# Sheet1.net
KiCad netlist of a schematic drawn in Altium Designer
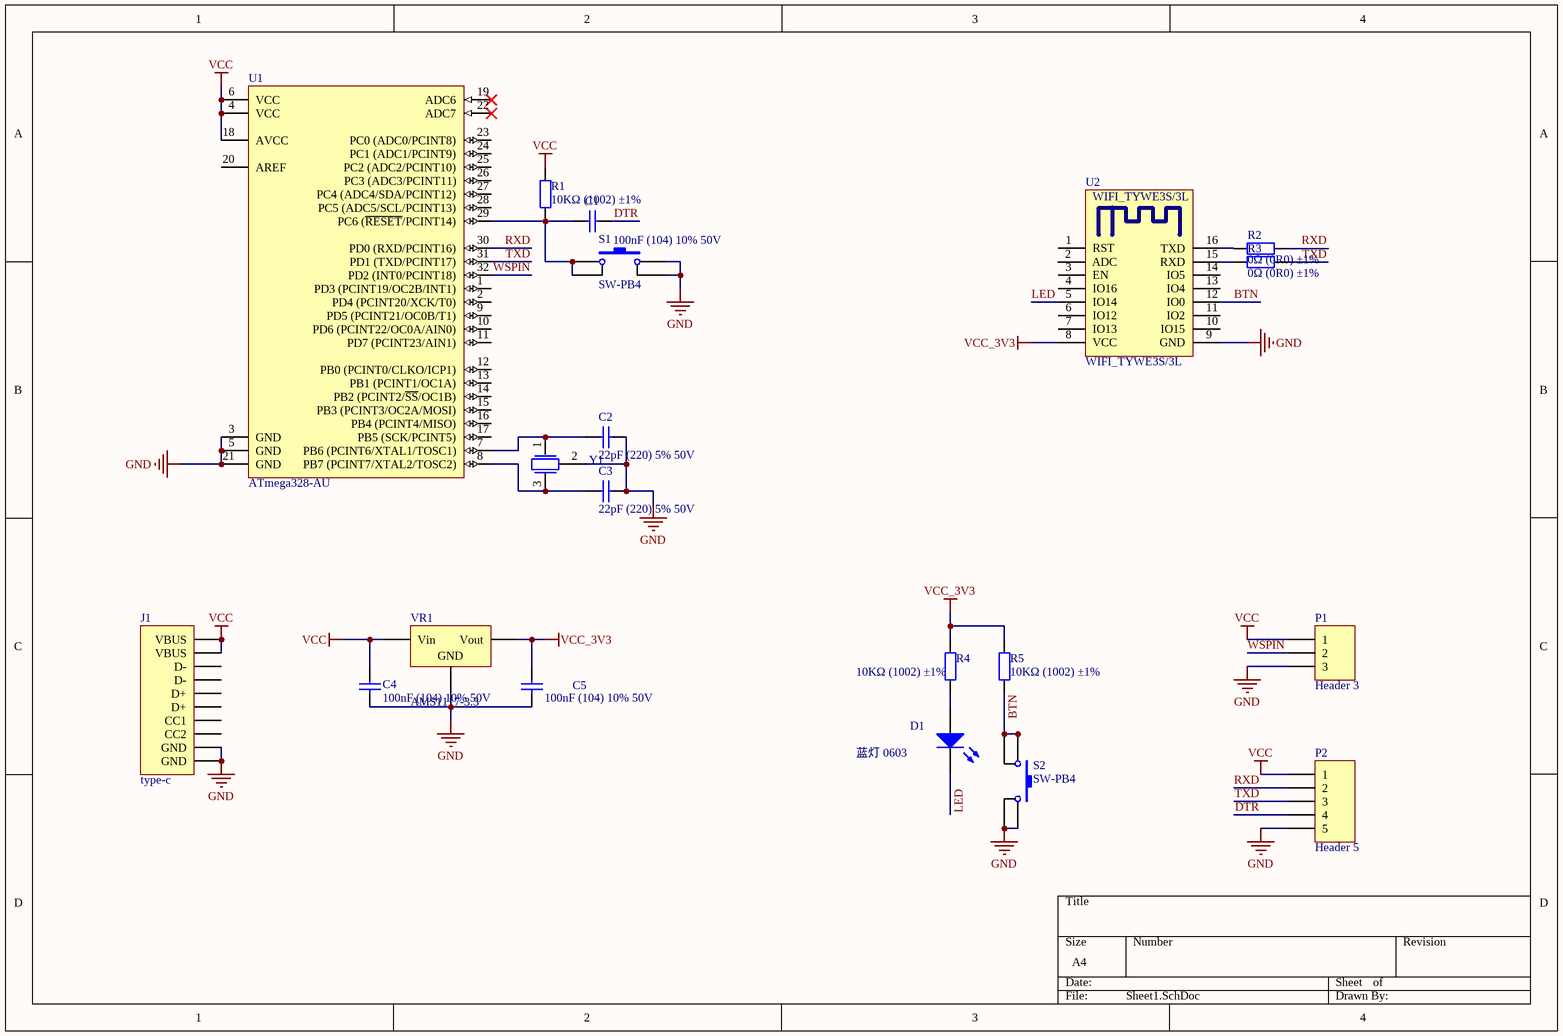
[diagram p0: Sheet1.SchDoc]

(export (version "E")
  (design (tool "Eeschema 10.0.6"))
  (components
    (comp (ref "C1")
      (value "100nF (104) 10% 50V")
      (footprint "LC-0603_C")
      (description "贴片电容")
      (libsource (lib "嘉立创库") (part "0603 100nF (104) 10% 50V"))
    )
    (comp (ref "C2")
      (value "22pF (220) 5% 50V")
      (footprint "LC-0603_C")
      (description "贴片电容")
      (libsource (lib "嘉立创库") (part "0603 22pF (220) 5% 50V"))
    )
    (comp (ref "C3")
      (value "22pF (220) 5% 50V")
      (footprint "LC-0603_C")
      (description "贴片电容")
      (libsource (lib "嘉立创库") (part "0603 22pF (220) 5% 50V"))
    )
    (comp (ref "C4")
      (value "100nF (104) 10% 50V")
      (footprint "LC-0603_C")
      (description "贴片电容")
      (libsource (lib "嘉立创库") (part "0603 100nF (104) 10% 50V"))
    )
    (comp (ref "C5")
      (value "100nF (104) 10% 50V")
      (footprint "LC-0603_C")
      (description "贴片电容")
      (libsource (lib "嘉立创库") (part "0603 100nF (104) 10% 50V"))
    )
    (comp (ref "D1")
      (value "蓝灯 0603")
      (footprint "LC-0603_LED_S1")
      (description "发光二极管")
      (libsource (lib "嘉立创库") (part "0603 蓝灯"))
    )
    (comp (ref "J1") (value "type-c") (footprint "type") (libsource (lib "Schlib_hqs") (part "type-c")))
    (comp (ref "P1")
      (value "Header 3")
      (footprint "XH2.54 3P")
      (description "Header, 3-Pin")
      (fields (field (name "PUBLISHER") "Altium Limited"))
      (libsource (lib "Miscellaneous Connectors") (part "Header 3"))
    )
    (comp (ref "P2")
      (value "Header 5")
      (footprint "HDR1X5")
      (description "Header, 5-Pin")
      (fields (field (name "PUBLISHER") "Altium Limited"))
      (libsource (lib "Miscellaneous Connectors") (part "Header 5"))
    )
    (comp (ref "R1")
      (value "10KΩ (1002) ±1%")
      (footprint "LC-0603_R")
      (description "贴片电阻")
      (libsource (lib "") (part "0603 10KΩ (1002) 1%_1"))
    )
    (comp (ref "R2")
      (value "0Ω (0R0) ±1%")
      (footprint "LC-0603_R")
      (description "贴片电阻")
      (libsource (lib "嘉立创库") (part "0603 0Ω (0R0) 1%"))
    )
    (comp (ref "R3")
      (value "0Ω (0R0) ±1%")
      (footprint "LC-0603_R")
      (description "贴片电阻")
      (libsource (lib "嘉立创库") (part "0603 0Ω (0R0) 1%"))
    )
    (comp (ref "R4")
      (value "10KΩ (1002) ±1%")
      (footprint "LC-0603_R")
      (description "贴片电阻")
      (libsource (lib "嘉立创库") (part "0603 10KΩ (1002) 1%"))
    )
    (comp (ref "R5")
      (value "10KΩ (1002) ±1%")
      (footprint "LC-0603_R")
      (description "贴片电阻")
      (libsource (lib "") (part "0603 10KΩ (1002) 1%_1"))
    )
    (comp (ref "S1")
      (value "SW-PB4")
      (footprint "SW_PB4_A1")
      (description "微动开关")
      (fields (field (name "PUBLISHER") "Altium Limited"))
      (libsource (lib "Fszhang") (part "SW-PB4"))
    )
    (comp (ref "S2")
      (value "SW-PB4")
      (footprint "SW_PB4_A1")
      (description "微动开关")
      (fields (field (name "PUBLISHER") "Altium Limited"))
      (libsource (lib "Fszhang") (part "SW-PB4"))
    )
    (comp (ref "U1")
      (value "ATmega328-AU")
      (footprint "32A_N")
      (fields (field (name "PUBLISHER") "Altium Limited"))
      (libsource (lib "Atmel Microcontroller 8-Bit megaAVR") (part "ATmega328-AU"))
    )
    (comp (ref "U2")
      (value "WIFI_TYWE3S/3L")
      (footprint "WIFI_TYWE3S/3L")
      (description "Module")
      (libsource (lib "TYModeSchlib") (part "WIFI_TYWE3S/3L"))
    )
    (comp (ref "VR1")
      (value "AMS1117-3.3")
      (footprint "LC-SOT-223")
      (description "低压差线性稳压(LDO)")
      (libsource (lib "嘉立创库") (part "SOT-223 AMS1117-3.3"))
    )
    (comp (ref "Y1")
      (value "XTAL-3PIN")
      (footprint "X-CPX20")
      (description "贴片晶振")
      (libsource (lib "Fszhang") (part "XTAL-3PIN"))
    )
  )
  (nets
    (net (code "1") (name "/BTN") (class "Default")
      (node (ref "R5") (pin "1") (pinfunction "1_1") (pintype "passive"))
      (node (ref "S2") (pin "1") (pinfunction "1_1") (pintype "passive"))
      (node (ref "S2") (pin "4") (pinfunction "4_4") (pintype "passive"))
      (node (ref "U2") (pin "12") (pinfunction "IO0_12") (pintype "passive"))
    )
    (net (code "2") (name "/DTR") (class "Default")
      (node (ref "C1") (pin "1") (pinfunction "1_1") (pintype "passive"))
      (node (ref "P2") (pin "4") (pinfunction "4_4") (pintype "passive"))
    )
    (net (code "3") (name "/LED") (class "Default")
      (node (ref "D1") (pin "K") (pinfunction "K_K") (pintype "passive"))
      (node (ref "U2") (pin "5") (pinfunction "IO14_5") (pintype "passive"))
    )
    (net (code "4") (name "/RXD") (class "Default")
      (node (ref "P2") (pin "2") (pinfunction "2_2") (pintype "passive"))
      (node (ref "R2") (pin "2") (pinfunction "2_2") (pintype "passive"))
      (node (ref "U1") (pin "30") (pinfunction "PD0_(RXD/PCINT16)_30") (pintype "bidirectional"))
    )
    (net (code "5") (name "/TXD") (class "Default")
      (node (ref "P2") (pin "3") (pinfunction "3_3") (pintype "passive"))
      (node (ref "R3") (pin "2") (pinfunction "2_2") (pintype "passive"))
      (node (ref "U1") (pin "31") (pinfunction "PD1_(TXD/PCINT17)_31") (pintype "bidirectional"))
    )
    (net (code "6") (name "/WSPIN") (class "Default")
      (node (ref "P1") (pin "2") (pinfunction "2_2") (pintype "passive"))
      (node (ref "U1") (pin "32") (pinfunction "PD2_(INT0/PCINT18)_32") (pintype "bidirectional"))
    )
    (net (code "7") (name "GND") (class "Default")
      (node (ref "C2") (pin "2") (pinfunction "2_2") (pintype "passive"))
      (node (ref "C3") (pin "2") (pinfunction "2_2") (pintype "passive"))
      (node (ref "C4") (pin "1") (pinfunction "1_1") (pintype "passive"))
      (node (ref "C5") (pin "1") (pinfunction "1_1") (pintype "passive"))
      (node (ref "J1") (pin "A12B1") (pinfunction "GND_A12B1") (pintype "passive"))
      (node (ref "J1") (pin "A1B12") (pinfunction "GND_A1B12") (pintype "passive"))
      (node (ref "P1") (pin "3") (pinfunction "3_3") (pintype "passive"))
      (node (ref "P2") (pin "5") (pinfunction "5_5") (pintype "passive"))
      (node (ref "S1") (pin "2") (pinfunction "2_2") (pintype "passive"))
      (node (ref "S1") (pin "3") (pinfunction "3_3") (pintype "passive"))
      (node (ref "S2") (pin "2") (pinfunction "2_2") (pintype "passive"))
      (node (ref "S2") (pin "3") (pinfunction "3_3") (pintype "passive"))
      (node (ref "U1") (pin "21") (pinfunction "GND_21") (pintype "power_in"))
      (node (ref "U1") (pin "3") (pinfunction "GND_3") (pintype "power_in"))
      (node (ref "U1") (pin "5") (pinfunction "GND_5") (pintype "power_in"))
      (node (ref "U2") (pin "9") (pinfunction "GND_9") (pintype "passive"))
      (node (ref "VR1") (pin "1") (pinfunction "GND_1") (pintype "passive"))
      (node (ref "Y1") (pin "2") (pinfunction "2_2") (pintype "passive"))
    )
    (net (code "8") (name "Net-(D1-PadA)") (class "Default")
      (node (ref "D1") (pin "A") (pinfunction "A_A") (pintype "passive"))
      (node (ref "R4") (pin "2") (pinfunction "2_2") (pintype "passive"))
    )
    (net (code "9") (name "Net-(U1-PB6_(PCINT6{slash}XTAL1{slash}TOSC1))") (class "Default")
      (node (ref "C2") (pin "1") (pinfunction "1_1") (pintype "passive"))
      (node (ref "U1") (pin "7") (pinfunction "PB6_(PCINT6/XTAL1/TOSC1)_7") (pintype "bidirectional"))
      (node (ref "Y1") (pin "1") (pinfunction "1_1") (pintype "passive"))
    )
    (net (code "10") (name "Net-(U1-PB7_(PCINT7{slash}XTAL2{slash}TOSC2))") (class "Default")
      (node (ref "C3") (pin "1") (pinfunction "1_1") (pintype "passive"))
      (node (ref "U1") (pin "8") (pinfunction "PB7_(PCINT7/XTAL2/TOSC2)_8") (pintype "bidirectional"))
      (node (ref "Y1") (pin "3") (pinfunction "3_3") (pintype "passive"))
    )
    (net (code "11") (name "Net-(U1-PC6_(~{RESET}{slash}PCINT14))") (class "Default")
      (node (ref "C1") (pin "2") (pinfunction "2_2") (pintype "passive"))
      (node (ref "R1") (pin "1") (pinfunction "1_1") (pintype "passive"))
      (node (ref "S1") (pin "1") (pinfunction "1_1") (pintype "passive"))
      (node (ref "S1") (pin "4") (pinfunction "4_4") (pintype "passive"))
      (node (ref "U1") (pin "29") (pinfunction "PC6_(~{RESET}/PCINT14)_29") (pintype "bidirectional"))
    )
    (net (code "12") (name "Net-(U2-RXD)") (class "Default")
      (node (ref "R3") (pin "1") (pinfunction "1_1") (pintype "passive"))
      (node (ref "U2") (pin "15") (pinfunction "RXD_15") (pintype "passive"))
    )
    (net (code "13") (name "Net-(U2-TXD)") (class "Default")
      (node (ref "R2") (pin "1") (pinfunction "1_1") (pintype "passive"))
      (node (ref "U2") (pin "16") (pinfunction "TXD_16") (pintype "passive"))
    )
    (net (code "14") (name "VCC") (class "Default")
      (node (ref "C4") (pin "2") (pinfunction "2_2") (pintype "passive"))
      (node (ref "J1") (pin "A4B9") (pinfunction "VBUS_A4B9") (pintype "passive"))
      (node (ref "J1") (pin "A9B4") (pinfunction "VBUS_A9B4") (pintype "passive"))
      (node (ref "P1") (pin "1") (pinfunction "1_1") (pintype "passive"))
      (node (ref "P2") (pin "1") (pinfunction "1_1") (pintype "passive"))
      (node (ref "R1") (pin "2") (pinfunction "2_2") (pintype "passive"))
      (node (ref "U1") (pin "18") (pinfunction "AVCC_18") (pintype "power_in"))
      (node (ref "U1") (pin "4") (pinfunction "VCC_4") (pintype "power_in"))
      (node (ref "U1") (pin "6") (pinfunction "VCC_6") (pintype "power_in"))
      (node (ref "VR1") (pin "3") (pinfunction "Vin_3") (pintype "passive"))
    )
    (net (code "15") (name "VCC_3V3") (class "Default")
      (node (ref "C5") (pin "2") (pinfunction "2_2") (pintype "passive"))
      (node (ref "R4") (pin "1") (pinfunction "1_1") (pintype "passive"))
      (node (ref "R5") (pin "2") (pinfunction "2_2") (pintype "passive"))
      (node (ref "U2") (pin "8") (pinfunction "VCC_8") (pintype "passive"))
      (node (ref "VR1") (pin "2") (pinfunction "Vout_2") (pintype "passive"))
    )
    (net (code "16") (name "unconnected-(J1-CC1-PadA5)") (class "Default")
      (node (ref "J1") (pin "A5") (pinfunction "CC1_A5") (pintype "passive"))
    )
    (net (code "17") (name "unconnected-(J1-CC2-PadB5)") (class "Default")
      (node (ref "J1") (pin "B5") (pinfunction "CC2_B5") (pintype "passive"))
    )
    (net (code "18") (name "unconnected-(J1-D+-PadA6)") (class "Default")
      (node (ref "J1") (pin "A6") (pinfunction "D+_A6") (pintype "passive"))
    )
    (net (code "19") (name "unconnected-(J1-D+-PadB6)") (class "Default")
      (node (ref "J1") (pin "B6") (pinfunction "D+_B6") (pintype "passive"))
    )
    (net (code "20") (name "unconnected-(J1-D--PadA7)") (class "Default")
      (node (ref "J1") (pin "A7") (pinfunction "D-_A7") (pintype "passive"))
    )
    (net (code "21") (name "unconnected-(J1-D--PadB7)") (class "Default")
      (node (ref "J1") (pin "B7") (pinfunction "D-_B7") (pintype "passive"))
    )
    (net (code "22") (name "unconnected-(U1-ADC6-Pad19)") (class "Default")
      (node (ref "U1") (pin "19") (pinfunction "ADC6_19") (pintype "input+no_connect"))
    )
    (net (code "23") (name "unconnected-(U1-ADC7-Pad22)") (class "Default")
      (node (ref "U1") (pin "22") (pinfunction "ADC7_22") (pintype "input+no_connect"))
    )
    (net (code "24") (name "unconnected-(U1-AREF-Pad20)") (class "Default")
      (node (ref "U1") (pin "20") (pinfunction "AREF_20") (pintype "passive"))
    )
    (net (code "25") (name "unconnected-(U1-PB0_(PCINT0{slash}CLKO{slash}ICP1)-Pad12)") (class "Default")
      (node (ref "U1") (pin "12") (pinfunction "PB0_(PCINT0/CLKO/ICP1)_12") (pintype "bidirectional"))
    )
    (net (code "26") (name "unconnected-(U1-PB1_(PCINT1{slash}OC1A)-Pad13)") (class "Default")
      (node (ref "U1") (pin "13") (pinfunction "PB1_(PCINT1/OC1A)_13") (pintype "bidirectional"))
    )
    (net (code "27") (name "unconnected-(U1-PB2_(PCINT2{slash}~{SS}{slash}OC1B)-Pad14)") (class "Default")
      (node (ref "U1") (pin "14") (pinfunction "PB2_(PCINT2/~{SS}/OC1B)_14") (pintype "bidirectional"))
    )
    (net (code "28") (name "unconnected-(U1-PB3_(PCINT3{slash}OC2A{slash}MOSI)-Pad15)") (class "Default")
      (node (ref "U1") (pin "15") (pinfunction "PB3_(PCINT3/OC2A/MOSI)_15") (pintype "bidirectional"))
    )
    (net (code "29") (name "unconnected-(U1-PB4_(PCINT4{slash}MISO)-Pad16)") (class "Default")
      (node (ref "U1") (pin "16") (pinfunction "PB4_(PCINT4/MISO)_16") (pintype "bidirectional"))
    )
    (net (code "30") (name "unconnected-(U1-PB5_(SCK{slash}PCINT5)-Pad17)") (class "Default")
      (node (ref "U1") (pin "17") (pinfunction "PB5_(SCK/PCINT5)_17") (pintype "bidirectional"))
    )
    (net (code "31") (name "unconnected-(U1-PC0_(ADC0{slash}PCINT8)-Pad23)") (class "Default")
      (node (ref "U1") (pin "23") (pinfunction "PC0_(ADC0/PCINT8)_23") (pintype "bidirectional"))
    )
    (net (code "32") (name "unconnected-(U1-PC1_(ADC1{slash}PCINT9)-Pad24)") (class "Default")
      (node (ref "U1") (pin "24") (pinfunction "PC1_(ADC1/PCINT9)_24") (pintype "bidirectional"))
    )
    (net (code "33") (name "unconnected-(U1-PC2_(ADC2{slash}PCINT10)-Pad25)") (class "Default")
      (node (ref "U1") (pin "25") (pinfunction "PC2_(ADC2/PCINT10)_25") (pintype "bidirectional"))
    )
    (net (code "34") (name "unconnected-(U1-PC3_(ADC3{slash}PCINT11)-Pad26)") (class "Default")
      (node (ref "U1") (pin "26") (pinfunction "PC3_(ADC3/PCINT11)_26") (pintype "bidirectional"))
    )
    (net (code "35") (name "unconnected-(U1-PC4_(ADC4{slash}SDA{slash}PCINT12)-Pad27)") (class "Default")
      (node (ref "U1") (pin "27") (pinfunction "PC4_(ADC4/SDA/PCINT12)_27") (pintype "bidirectional"))
    )
    (net (code "36") (name "unconnected-(U1-PC5_(ADC5{slash}SCL{slash}PCINT13)-Pad28)") (class "Default")
      (node (ref "U1") (pin "28") (pinfunction "PC5_(ADC5/SCL/PCINT13)_28") (pintype "bidirectional"))
    )
    (net (code "37") (name "unconnected-(U1-PD3_(PCINT19{slash}OC2B{slash}INT1)-Pad1)") (class "Default")
      (node (ref "U1") (pin "1") (pinfunction "PD3_(PCINT19/OC2B/INT1)_1") (pintype "bidirectional"))
    )
    (net (code "38") (name "unconnected-(U1-PD4_(PCINT20{slash}XCK{slash}T0)-Pad2)") (class "Default")
      (node (ref "U1") (pin "2") (pinfunction "PD4_(PCINT20/XCK/T0)_2") (pintype "bidirectional"))
    )
    (net (code "39") (name "unconnected-(U1-PD5_(PCINT21{slash}OC0B{slash}T1)-Pad9)") (class "Default")
      (node (ref "U1") (pin "9") (pinfunction "PD5_(PCINT21/OC0B/T1)_9") (pintype "bidirectional"))
    )
    (net (code "40") (name "unconnected-(U1-PD6_(PCINT22{slash}OC0A{slash}AIN0)-Pad10)") (class "Default")
      (node (ref "U1") (pin "10") (pinfunction "PD6_(PCINT22/OC0A/AIN0)_10") (pintype "bidirectional"))
    )
    (net (code "41") (name "unconnected-(U1-PD7_(PCINT23{slash}AIN1)-Pad11)") (class "Default")
      (node (ref "U1") (pin "11") (pinfunction "PD7_(PCINT23/AIN1)_11") (pintype "bidirectional"))
    )
    (net (code "42") (name "unconnected-(U2-ADC-Pad2)") (class "Default")
      (node (ref "U2") (pin "2") (pinfunction "ADC_2") (pintype "passive"))
    )
    (net (code "43") (name "unconnected-(U2-EN-Pad3)") (class "Default")
      (node (ref "U2") (pin "3") (pinfunction "EN_3") (pintype "passive"))
    )
    (net (code "44") (name "unconnected-(U2-IO2-Pad11)") (class "Default")
      (node (ref "U2") (pin "11") (pinfunction "IO2_11") (pintype "passive"))
    )
    (net (code "45") (name "unconnected-(U2-IO4-Pad13)") (class "Default")
      (node (ref "U2") (pin "13") (pinfunction "IO4_13") (pintype "passive"))
    )
    (net (code "46") (name "unconnected-(U2-IO5-Pad14)") (class "Default")
      (node (ref "U2") (pin "14") (pinfunction "IO5_14") (pintype "passive"))
    )
    (net (code "47") (name "unconnected-(U2-IO12-Pad6)") (class "Default")
      (node (ref "U2") (pin "6") (pinfunction "IO12_6") (pintype "passive"))
    )
    (net (code "48") (name "unconnected-(U2-IO13-Pad7)") (class "Default")
      (node (ref "U2") (pin "7") (pinfunction "IO13_7") (pintype "passive"))
    )
    (net (code "49") (name "unconnected-(U2-IO15-Pad10)") (class "Default")
      (node (ref "U2") (pin "10") (pinfunction "IO15_10") (pintype "passive"))
    )
    (net (code "50") (name "unconnected-(U2-IO16-Pad4)") (class "Default")
      (node (ref "U2") (pin "4") (pinfunction "IO16_4") (pintype "passive"))
    )
    (net (code "51") (name "unconnected-(U2-RST-Pad1)") (class "Default")
      (node (ref "U2") (pin "1") (pinfunction "RST_1") (pintype "passive"))
    )
  )
)
